# CM_MODULE.net
KiCad netlist of a schematic drawn in Altium Designer
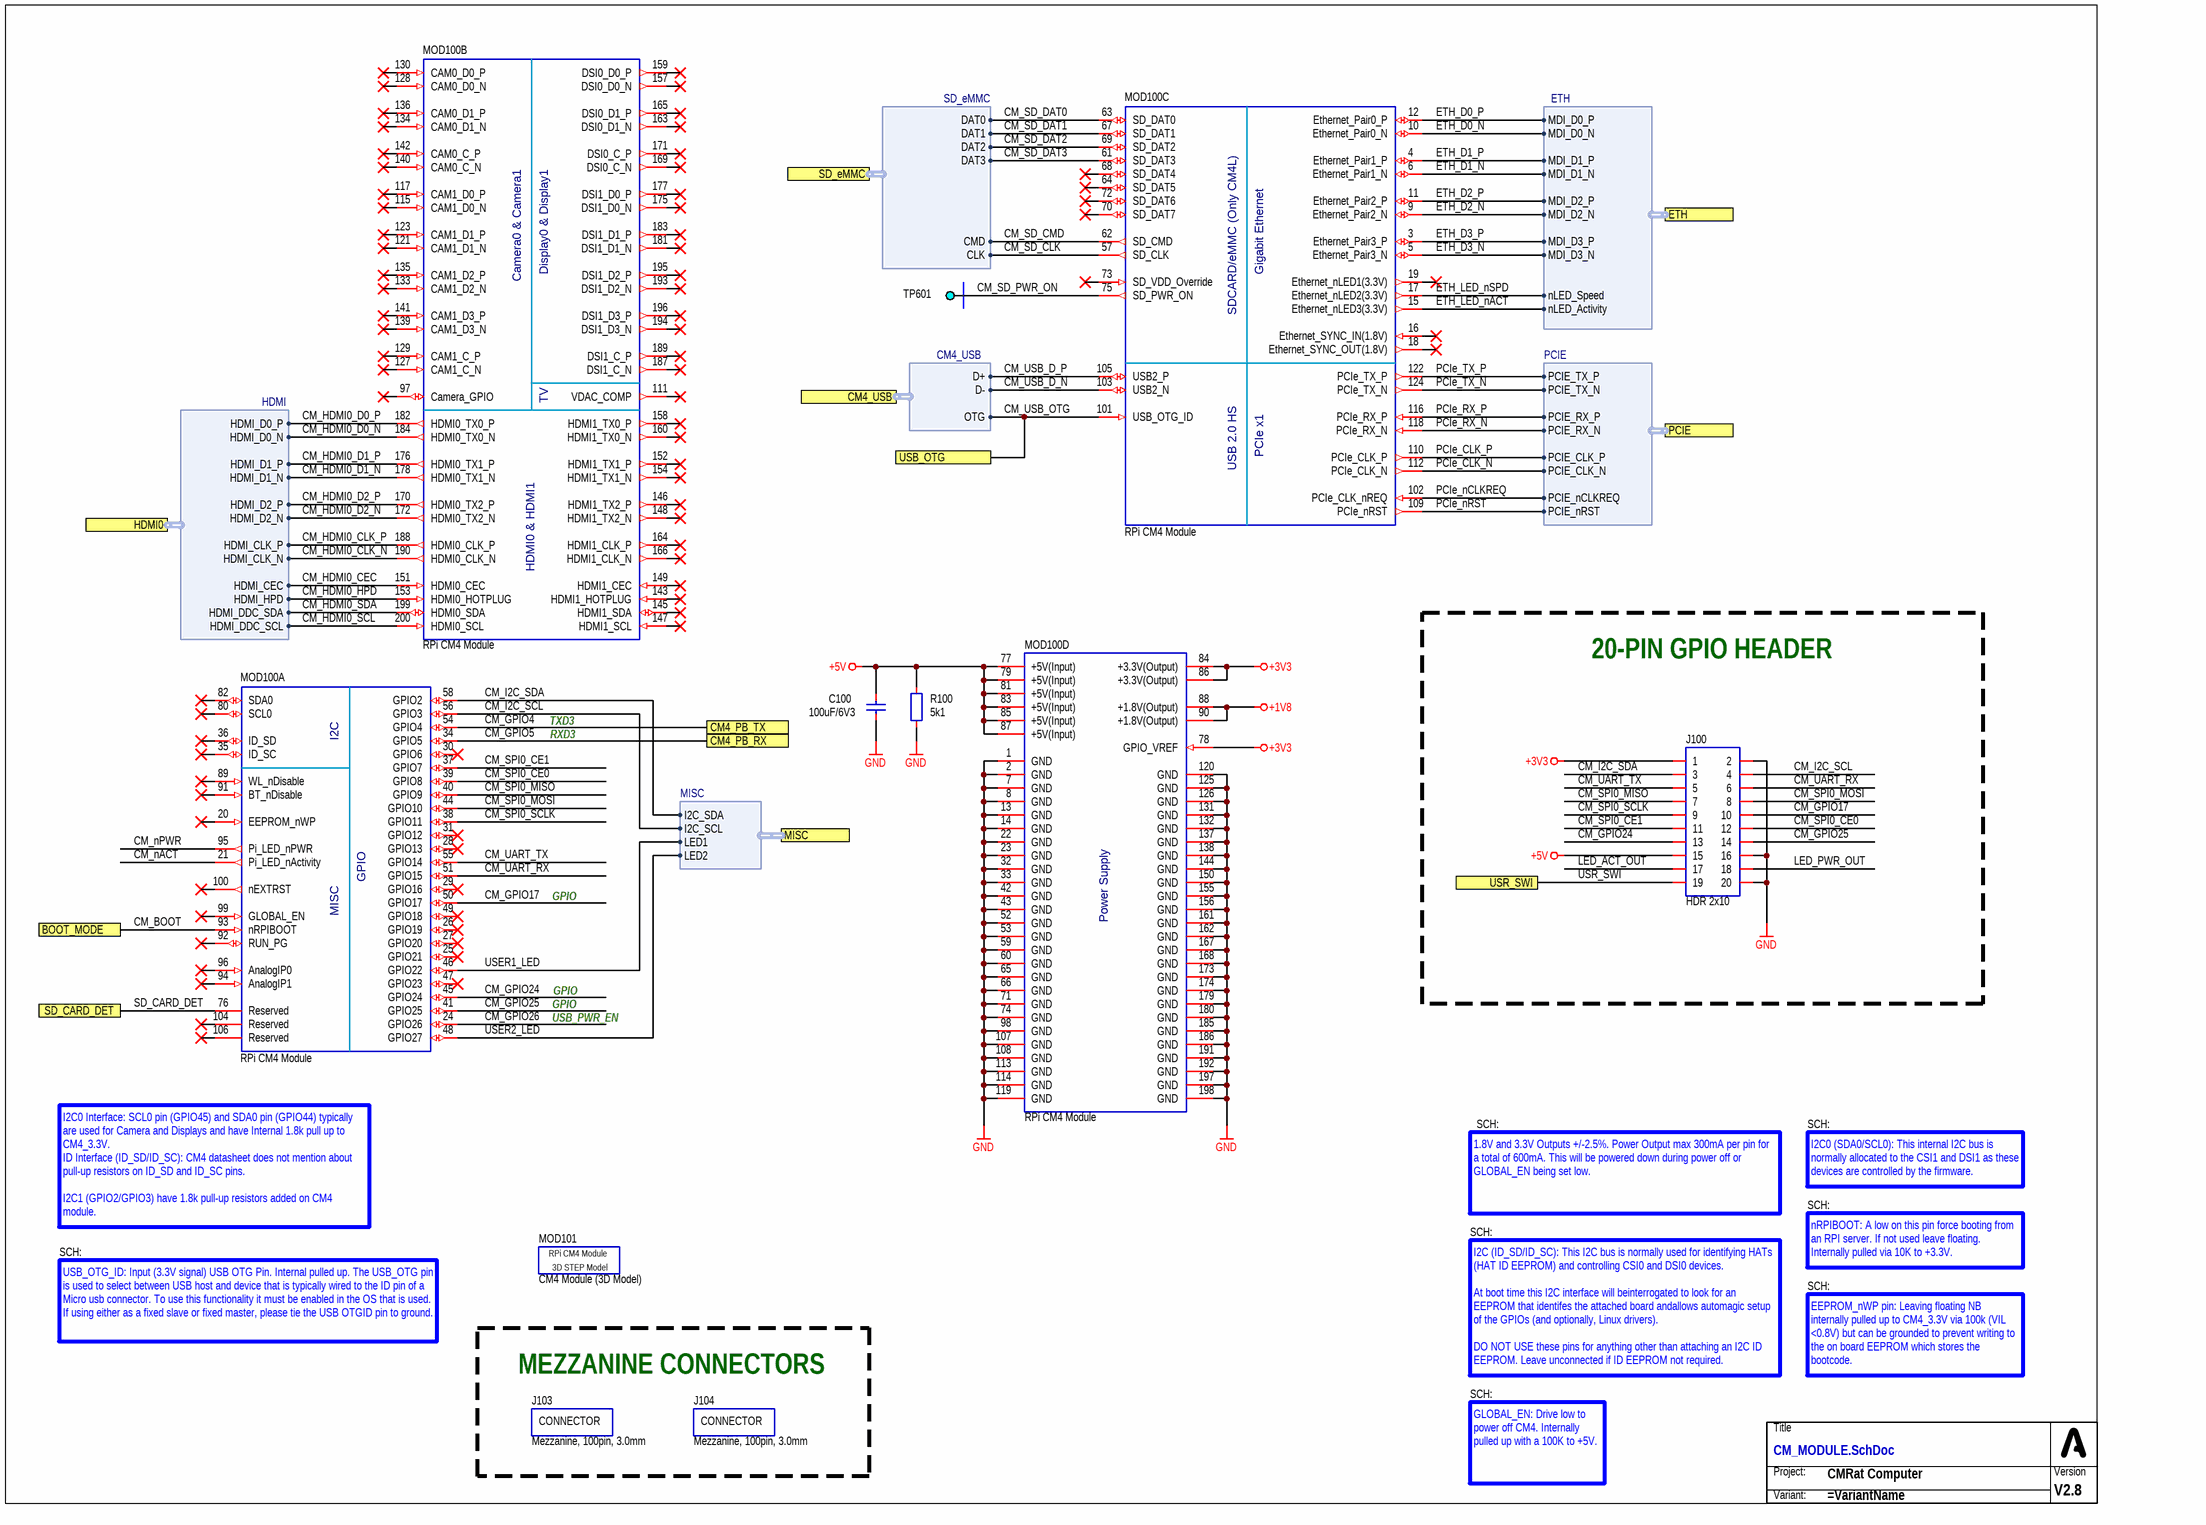
[diagram p0: CM_MODULE.SchDoc]

(export (version "E")
  (design (tool "Eeschema 10.0.6"))
  (components
    (comp (ref "C100")
      (value "100uF/6V3")
      (footprint "CAP_1206_R")
      (description "Capacitor; MLCC; 100uF 6V3")
      (fields (field (name "MANUFACTURER") "Taiyo Yuden") (field (name "MPN") "JMK316ABJ107ML-T"))
      (libsource (lib "MirFol_db_local") (part "CAP"))
    )
    (comp (ref "J100")
      (value "HDR 2x10")
      (footprint "CON_HDR_P254_2X10_STR")
      (description "CONN THT / HEADER / PITCH 2,54mm / VERTICAL / (20 PIN) 2x10")
      (fields
        (field (name "MPN") "B-2100S20P-B110")
        (field (name "MANUFACTURER") "Ckmtw(Shenzhen Cankemeng)")
      )
      (libsource (lib "MirFol_lib") (part "CON_2X10_ROW"))
    )
    (comp (ref "J103")
      (value "Mezzanine, 100pin, 3.0mm")
      (footprint "PCB_BLANK_COMP_SMD")
      (description "Connector; DF40HC(3.0)-100DS-0.4V")
      (fields (field (name "MANUFACTURER") "Hirose") (field (name "MPN") "DF40HC(3.0)-100DS-0.4V"))
      (libsource (lib "MirFol_lib") (part "BOM_CON"))
    )
    (comp (ref "J104")
      (value "Mezzanine, 100pin, 3.0mm")
      (footprint "PCB_BLANK_COMP_SMD")
      (description "Connector; DF40HC(3.0)-100DS-0.4V")
      (fields (field (name "MANUFACTURER") "Hirose") (field (name "MPN") "DF40HC(3.0)-100DS-0.4V"))
      (libsource (lib "MirFol_lib") (part "BOM_CON"))
    )
    (comp (ref "MOD100")
      (value "RPi CM4 Module")
      (footprint "MOD_RPI_CM4_SOCKET_P40_C300")
      (description "PCB Module; RPi Compute Module 4;")
      (fields (field (name "MPN") "CM4 Module") (field (name "MANUFACTURER") "Raspberry Pi Foundation"))
      (libsource (lib "MirFol_lib") (part "MOD_RPI_CM4_VAR2"))
    )
    (comp (ref "MOD101")
      (value "CM4 Module (3D Model)")
      (footprint "MOD_RPI_CM4_3D_C300_A1")
      (description "PCB Module; RPi Compute Module 4; 3D model")
      (libsource (lib "Pineberry_Lib") (part "MOD_CM4_3D_MODEL"))
    )
    (comp (ref "R100")
      (value "5k1")
      (footprint "RES_0603_R")
      (description "Resistor; Thick Film; 5k1; 1%; 100mW; 100PPM; 75V; Standard; SMD; 0603 (1608);")
      (fields (field (name "MANUFACTURER") "UNI-ROYAL(Uniroyal Elec)") (field (name "MPN") "0603WAF5101T5E"))
      (libsource (lib "MirFol_db_local") (part "RES"))
    )
    (comp (ref "TB100") (value "~") (libsource (lib "Symbols_NO_BOM") (part "SCH_TITLE_BLOCK_SIMPLE_NODATE")))
    (comp (ref "TP601")
      (value "DEBUG")
      (footprint "PCB_TP_DBG_50")
      (description "PCB Marking; Test Point (Debug);")
      (libsource (lib "MirFol_lib") (part "PCB_TP_DBG"))
    )
  )
  (nets
    (net (code "7") (name "+1V8") (class "Default")
      (node (ref "MOD100") (pin "88") (pinfunction "+1.8V(Output)_88") (pintype "power_in"))
      (node (ref "MOD100") (pin "90") (pinfunction "+1.8V(Output)_90") (pintype "power_in"))
    )
    (net (code "8") (name "+3V3") (class "Default")
      (node (ref "J100") (pin "1") (pinfunction "1_1") (pintype "passive"))
      (node (ref "MOD100") (pin "78") (pinfunction "GPIO_VREF_78") (pintype "input"))
      (node (ref "MOD100") (pin "84") (pinfunction "+3.3V(Output)_84") (pintype "power_in"))
      (node (ref "MOD100") (pin "86") (pinfunction "+3.3V(Output)_86") (pintype "power_in"))
    )
    (net (code "9") (name "+5V") (class "Default")
      (node (ref "C100") (pin "2") (pintype "passive"))
      (node (ref "J100") (pin "15") (pinfunction "15_15") (pintype "passive"))
      (node (ref "MOD100") (pin "77") (pinfunction "+5V(Input)_77") (pintype "power_in"))
      (node (ref "MOD100") (pin "79") (pinfunction "+5V(Input)_79") (pintype "power_in"))
      (node (ref "MOD100") (pin "81") (pinfunction "+5V(Input)_81") (pintype "power_in"))
      (node (ref "MOD100") (pin "83") (pinfunction "+5V(Input)_83") (pintype "power_in"))
      (node (ref "MOD100") (pin "85") (pinfunction "+5V(Input)_85") (pintype "power_in"))
      (node (ref "MOD100") (pin "87") (pinfunction "+5V(Input)_87") (pintype "power_in"))
      (node (ref "R100") (pin "1") (pinfunction "1_1") (pintype "passive"))
    )
    (net (code "10") (name "/CM_BOOT") (class "Default")
      (node (ref "MOD100") (pin "93") (pinfunction "nRPIBOOT_93") (pintype "input"))
    )
    (net (code "11") (name "/CM_GPIO4") (class "Default")
      (node (ref "MOD100") (pin "54") (pinfunction "GPIO4_54") (pintype "bidirectional"))
    )
    (net (code "12") (name "/CM_GPIO5") (class "Default")
      (node (ref "MOD100") (pin "34") (pinfunction "GPIO5_34") (pintype "bidirectional"))
    )
    (net (code "13") (name "/CM_GPIO17") (class "Default")
      (node (ref "J100") (pin "10") (pinfunction "10_10") (pintype "passive"))
      (node (ref "MOD100") (pin "50") (pinfunction "GPIO17_50") (pintype "bidirectional"))
    )
    (net (code "14") (name "/CM_GPIO24") (class "Default")
      (node (ref "J100") (pin "13") (pinfunction "13_13") (pintype "passive"))
      (node (ref "MOD100") (pin "45") (pinfunction "GPIO24_45") (pintype "bidirectional"))
    )
    (net (code "15") (name "/CM_GPIO25") (class "Default")
      (node (ref "J100") (pin "14") (pinfunction "14_14") (pintype "passive"))
      (node (ref "MOD100") (pin "41") (pinfunction "GPIO25_41") (pintype "bidirectional"))
    )
    (net (code "16") (name "/CM_GPIO26") (class "Default")
      (node (ref "MOD100") (pin "24") (pinfunction "GPIO26_24") (pintype "bidirectional"))
    )
    (net (code "17") (name "/CM_HDMI0_CEC") (class "Default")
      (node (ref "MOD100") (pin "151") (pinfunction "HDMI0_CEC_151") (pintype "input"))
    )
    (net (code "18") (name "/CM_HDMI0_CLK_N") (class "Default")
      (node (ref "MOD100") (pin "190") (pinfunction "HDMI0_CLK_N_190") (pintype "output"))
    )
    (net (code "19") (name "/CM_HDMI0_CLK_P") (class "Default")
      (node (ref "MOD100") (pin "188") (pinfunction "HDMI0_CLK_P_188") (pintype "output"))
    )
    (net (code "20") (name "/CM_HDMI0_D0_N") (class "Default")
      (node (ref "MOD100") (pin "184") (pinfunction "HDMI0_TX0_N_184") (pintype "output"))
    )
    (net (code "21") (name "/CM_HDMI0_D0_P") (class "Default")
      (node (ref "MOD100") (pin "182") (pinfunction "HDMI0_TX0_P_182") (pintype "output"))
    )
    (net (code "22") (name "/CM_HDMI0_D1_N") (class "Default")
      (node (ref "MOD100") (pin "178") (pinfunction "HDMI0_TX1_N_178") (pintype "output"))
    )
    (net (code "23") (name "/CM_HDMI0_D1_P") (class "Default")
      (node (ref "MOD100") (pin "176") (pinfunction "HDMI0_TX1_P_176") (pintype "output"))
    )
    (net (code "24") (name "/CM_HDMI0_D2_N") (class "Default")
      (node (ref "MOD100") (pin "172") (pinfunction "HDMI0_TX2_N_172") (pintype "output"))
    )
    (net (code "25") (name "/CM_HDMI0_D2_P") (class "Default")
      (node (ref "MOD100") (pin "170") (pinfunction "HDMI0_TX2_P_170") (pintype "output"))
    )
    (net (code "26") (name "/CM_HDMI0_HPD") (class "Default")
      (node (ref "MOD100") (pin "153") (pinfunction "HDMI0_HOTPLUG_153") (pintype "input"))
    )
    (net (code "27") (name "/CM_HDMI0_SCL") (class "Default")
      (node (ref "MOD100") (pin "200") (pinfunction "HDMI0_SCL_200") (pintype "input"))
    )
    (net (code "28") (name "/CM_HDMI0_SDA") (class "Default")
      (node (ref "MOD100") (pin "199") (pinfunction "HDMI0_SDA_199") (pintype "bidirectional"))
    )
    (net (code "29") (name "/CM_I2C_SCL") (class "Default")
      (node (ref "J100") (pin "4") (pinfunction "4_4") (pintype "passive"))
      (node (ref "MOD100") (pin "56") (pinfunction "GPIO3_56") (pintype "bidirectional"))
    )
    (net (code "30") (name "/CM_I2C_SDA") (class "Default")
      (node (ref "J100") (pin "3") (pinfunction "3_3") (pintype "passive"))
      (node (ref "MOD100") (pin "58") (pinfunction "GPIO2_58") (pintype "bidirectional"))
    )
    (net (code "31") (name "/CM_SD_CLK") (class "Default")
      (node (ref "MOD100") (pin "57") (pinfunction "SD_CLK_57") (pintype "output"))
    )
    (net (code "32") (name "/CM_SD_CMD") (class "Default")
      (node (ref "MOD100") (pin "62") (pinfunction "SD_CMD_62") (pintype "output"))
    )
    (net (code "33") (name "/CM_SD_DAT0") (class "Default")
      (node (ref "MOD100") (pin "63") (pinfunction "SD_DAT0_63") (pintype "bidirectional"))
    )
    (net (code "34") (name "/CM_SD_DAT1") (class "Default")
      (node (ref "MOD100") (pin "67") (pinfunction "SD_DAT1_67") (pintype "bidirectional"))
    )
    (net (code "35") (name "/CM_SD_DAT2") (class "Default")
      (node (ref "MOD100") (pin "69") (pinfunction "SD_DAT2_69") (pintype "bidirectional"))
    )
    (net (code "36") (name "/CM_SD_DAT3") (class "Default")
      (node (ref "MOD100") (pin "61") (pinfunction "SD_DAT3_61") (pintype "bidirectional"))
    )
    (net (code "37") (name "/CM_SD_PWR_ON") (class "Default")
      (node (ref "MOD100") (pin "75") (pinfunction "SD_PWR_ON_75") (pintype "output"))
      (node (ref "TP601") (pin "1") (pinfunction "1_1") (pintype "passive"))
    )
    (net (code "38") (name "/CM_SPI0_CE0") (class "Default")
      (node (ref "J100") (pin "12") (pinfunction "12_12") (pintype "passive"))
      (node (ref "MOD100") (pin "39") (pinfunction "GPIO8_39") (pintype "bidirectional"))
    )
    (net (code "39") (name "/CM_SPI0_CE1") (class "Default")
      (node (ref "J100") (pin "11") (pinfunction "11_11") (pintype "passive"))
      (node (ref "MOD100") (pin "37") (pinfunction "GPIO7_37") (pintype "bidirectional"))
    )
    (net (code "40") (name "/CM_SPI0_MISO") (class "Default")
      (node (ref "J100") (pin "7") (pinfunction "7_7") (pintype "passive"))
      (node (ref "MOD100") (pin "40") (pinfunction "GPIO9_40") (pintype "bidirectional"))
    )
    (net (code "41") (name "/CM_SPI0_MOSI") (class "Default")
      (node (ref "J100") (pin "8") (pinfunction "8_8") (pintype "passive"))
      (node (ref "MOD100") (pin "44") (pinfunction "GPIO10_44") (pintype "bidirectional"))
    )
    (net (code "42") (name "/CM_SPI0_SCLK") (class "Default")
      (node (ref "J100") (pin "9") (pinfunction "9_9") (pintype "passive"))
      (node (ref "MOD100") (pin "38") (pinfunction "GPIO11_38") (pintype "bidirectional"))
    )
    (net (code "43") (name "/CM_UART_RX") (class "Default")
      (node (ref "J100") (pin "6") (pinfunction "6_6") (pintype "passive"))
      (node (ref "MOD100") (pin "51") (pinfunction "GPIO15_51") (pintype "bidirectional"))
    )
    (net (code "44") (name "/CM_UART_TX") (class "Default")
      (node (ref "J100") (pin "5") (pinfunction "5_5") (pintype "passive"))
      (node (ref "MOD100") (pin "55") (pinfunction "GPIO14_55") (pintype "bidirectional"))
    )
    (net (code "45") (name "/CM_USB_D_N") (class "Default")
      (node (ref "MOD100") (pin "103") (pinfunction "USB2_N_103") (pintype "bidirectional"))
    )
    (net (code "46") (name "/CM_USB_D_P") (class "Default")
      (node (ref "MOD100") (pin "105") (pinfunction "USB2_P_105") (pintype "bidirectional"))
    )
    (net (code "47") (name "/CM_USB_OTG") (class "Default")
      (node (ref "MOD100") (pin "101") (pinfunction "USB_OTG_ID_101") (pintype "input"))
    )
    (net (code "48") (name "/CM_nACT") (class "Default")
      (node (ref "MOD100") (pin "21") (pinfunction "Pi_LED_nActivity_21") (pintype "output"))
    )
    (net (code "49") (name "/CM_nPWR") (class "Default")
      (node (ref "MOD100") (pin "95") (pinfunction "Pi_LED_nPWR_95") (pintype "output"))
    )
    (net (code "50") (name "/ETH_D0_N") (class "Default")
      (node (ref "MOD100") (pin "10") (pinfunction "Ethernet_Pair0_N_10") (pintype "bidirectional"))
    )
    (net (code "51") (name "/ETH_D0_P") (class "Default")
      (node (ref "MOD100") (pin "12") (pinfunction "Ethernet_Pair0_P_12") (pintype "bidirectional"))
    )
    (net (code "52") (name "/ETH_D1_N") (class "Default")
      (node (ref "MOD100") (pin "6") (pinfunction "Ethernet_Pair1_N_6") (pintype "bidirectional"))
    )
    (net (code "53") (name "/ETH_D1_P") (class "Default")
      (node (ref "MOD100") (pin "4") (pinfunction "Ethernet_Pair1_P_4") (pintype "bidirectional"))
    )
    (net (code "54") (name "/ETH_D2_N") (class "Default")
      (node (ref "MOD100") (pin "9") (pinfunction "Ethernet_Pair2_N_9") (pintype "bidirectional"))
    )
    (net (code "55") (name "/ETH_D2_P") (class "Default")
      (node (ref "MOD100") (pin "11") (pinfunction "Ethernet_Pair2_P_11") (pintype "bidirectional"))
    )
    (net (code "56") (name "/ETH_D3_N") (class "Default")
      (node (ref "MOD100") (pin "5") (pinfunction "Ethernet_Pair3_N_5") (pintype "bidirectional"))
    )
    (net (code "57") (name "/ETH_D3_P") (class "Default")
      (node (ref "MOD100") (pin "3") (pinfunction "Ethernet_Pair3_P_3") (pintype "bidirectional"))
    )
    (net (code "58") (name "/ETH_LED_nACT") (class "Default")
      (node (ref "MOD100") (pin "15") (pinfunction "Ethernet_nLED3(3.3V)_15") (pintype "output"))
    )
    (net (code "59") (name "/ETH_LED_nSPD") (class "Default")
      (node (ref "MOD100") (pin "17") (pinfunction "Ethernet_nLED2(3.3V)_17") (pintype "output"))
    )
    (net (code "60") (name "/LED_ACT_OUT") (class "Default")
      (node (ref "J100") (pin "17") (pinfunction "17_17") (pintype "passive"))
    )
    (net (code "61") (name "/LED_PWR_OUT") (class "Default")
      (node (ref "J100") (pin "18") (pinfunction "18_18") (pintype "passive"))
    )
    (net (code "62") (name "/PCIe_CLK_N") (class "Default")
      (node (ref "MOD100") (pin "112") (pinfunction "PCIe_CLK_N_112") (pintype "output"))
    )
    (net (code "63") (name "/PCIe_CLK_P") (class "Default")
      (node (ref "MOD100") (pin "110") (pinfunction "PCIe_CLK_P_110") (pintype "output"))
    )
    (net (code "64") (name "/PCIe_RX_N") (class "Default")
      (node (ref "MOD100") (pin "118") (pinfunction "PCIe_RX_N_118") (pintype "input"))
    )
    (net (code "65") (name "/PCIe_RX_P") (class "Default")
      (node (ref "MOD100") (pin "116") (pinfunction "PCIe_RX_P_116") (pintype "input"))
    )
    (net (code "66") (name "/PCIe_TX_N") (class "Default")
      (node (ref "MOD100") (pin "124") (pinfunction "PCIe_TX_N_124") (pintype "output"))
    )
    (net (code "67") (name "/PCIe_TX_P") (class "Default")
      (node (ref "MOD100") (pin "122") (pinfunction "PCIe_TX_P_122") (pintype "output"))
    )
    (net (code "68") (name "/PCIe_nCLKREQ") (class "Default")
      (node (ref "MOD100") (pin "102") (pinfunction "PCIe_CLK_nREQ_102") (pintype "input"))
    )
    (net (code "69") (name "/PCIe_nRST") (class "Default")
      (node (ref "MOD100") (pin "109") (pinfunction "PCIe_nRST_109") (pintype "output"))
    )
    (net (code "70") (name "/SD_CARD_DET") (class "Default")
      (node (ref "MOD100") (pin "76") (pinfunction "Reserved_76") (pintype "passive"))
    )
    (net (code "71") (name "/USER1_LED") (class "Default")
      (node (ref "MOD100") (pin "46") (pinfunction "GPIO22_46") (pintype "bidirectional"))
    )
    (net (code "72") (name "/USER2_LED") (class "Default")
      (node (ref "MOD100") (pin "48") (pinfunction "GPIO27_48") (pintype "bidirectional"))
    )
    (net (code "73") (name "/USR_SWI") (class "Default")
      (node (ref "J100") (pin "19") (pinfunction "19_19") (pintype "passive"))
    )
    (net (code "80") (name "GND") (class "Default")
      (node (ref "C100") (pin "1") (pintype "passive"))
      (node (ref "J100") (pin "16") (pinfunction "16_16") (pintype "passive"))
      (node (ref "J100") (pin "2") (pinfunction "2_2") (pintype "passive"))
      (node (ref "J100") (pin "20") (pinfunction "20_20") (pintype "passive"))
      (node (ref "MOD100") (pin "1") (pinfunction "GND_1") (pintype "power_in"))
      (node (ref "MOD100") (pin "107") (pinfunction "GND_107") (pintype "power_in"))
      (node (ref "MOD100") (pin "108") (pinfunction "GND_108") (pintype "power_in"))
      (node (ref "MOD100") (pin "113") (pinfunction "GND_113") (pintype "power_in"))
      (node (ref "MOD100") (pin "114") (pinfunction "GND_114") (pintype "power_in"))
      (node (ref "MOD100") (pin "119") (pinfunction "GND_119") (pintype "power_in"))
      (node (ref "MOD100") (pin "120") (pinfunction "GND_120") (pintype "power_in"))
      (node (ref "MOD100") (pin "125") (pinfunction "GND_125") (pintype "power_in"))
      (node (ref "MOD100") (pin "126") (pinfunction "GND_126") (pintype "power_in"))
      (node (ref "MOD100") (pin "13") (pinfunction "GND_13") (pintype "power_in"))
      (node (ref "MOD100") (pin "131") (pinfunction "GND_131") (pintype "power_in"))
      (node (ref "MOD100") (pin "132") (pinfunction "GND_132") (pintype "power_in"))
      (node (ref "MOD100") (pin "137") (pinfunction "GND_137") (pintype "power_in"))
      (node (ref "MOD100") (pin "138") (pinfunction "GND_138") (pintype "power_in"))
      (node (ref "MOD100") (pin "14") (pinfunction "GND_14") (pintype "power_in"))
      (node (ref "MOD100") (pin "144") (pinfunction "GND_144") (pintype "power_in"))
      (node (ref "MOD100") (pin "150") (pinfunction "GND_150") (pintype "power_in"))
      (node (ref "MOD100") (pin "155") (pinfunction "GND_155") (pintype "power_in"))
      (node (ref "MOD100") (pin "156") (pinfunction "GND_156") (pintype "power_in"))
      (node (ref "MOD100") (pin "161") (pinfunction "GND_161") (pintype "power_in"))
      (node (ref "MOD100") (pin "162") (pinfunction "GND_162") (pintype "power_in"))
      (node (ref "MOD100") (pin "167") (pinfunction "GND_167") (pintype "power_in"))
      (node (ref "MOD100") (pin "168") (pinfunction "GND_168") (pintype "power_in"))
      (node (ref "MOD100") (pin "173") (pinfunction "GND_173") (pintype "power_in"))
      (node (ref "MOD100") (pin "174") (pinfunction "GND_174") (pintype "power_in"))
      (node (ref "MOD100") (pin "179") (pinfunction "GND_179") (pintype "power_in"))
      (node (ref "MOD100") (pin "180") (pinfunction "GND_180") (pintype "power_in"))
      (node (ref "MOD100") (pin "185") (pinfunction "GND_185") (pintype "power_in"))
      (node (ref "MOD100") (pin "186") (pinfunction "GND_186") (pintype "power_in"))
      (node (ref "MOD100") (pin "191") (pinfunction "GND_191") (pintype "power_in"))
      (node (ref "MOD100") (pin "192") (pinfunction "GND_192") (pintype "power_in"))
      (node (ref "MOD100") (pin "197") (pinfunction "GND_197") (pintype "power_in"))
      (node (ref "MOD100") (pin "198") (pinfunction "GND_198") (pintype "power_in"))
      (node (ref "MOD100") (pin "2") (pinfunction "GND_2") (pintype "power_in"))
      (node (ref "MOD100") (pin "22") (pinfunction "GND_22") (pintype "power_in"))
      (node (ref "MOD100") (pin "23") (pinfunction "GND_23") (pintype "power_in"))
      (node (ref "MOD100") (pin "32") (pinfunction "GND_32") (pintype "power_in"))
      (node (ref "MOD100") (pin "33") (pinfunction "GND_33") (pintype "power_in"))
      (node (ref "MOD100") (pin "42") (pinfunction "GND_42") (pintype "power_in"))
      (node (ref "MOD100") (pin "43") (pinfunction "GND_43") (pintype "power_in"))
      (node (ref "MOD100") (pin "52") (pinfunction "GND_52") (pintype "power_in"))
      (node (ref "MOD100") (pin "53") (pinfunction "GND_53") (pintype "power_in"))
      (node (ref "MOD100") (pin "59") (pinfunction "GND_59") (pintype "power_in"))
      (node (ref "MOD100") (pin "60") (pinfunction "GND_60") (pintype "power_in"))
      (node (ref "MOD100") (pin "65") (pinfunction "GND_65") (pintype "power_in"))
      (node (ref "MOD100") (pin "66") (pinfunction "GND_66") (pintype "power_in"))
      (node (ref "MOD100") (pin "7") (pinfunction "GND_7") (pintype "power_in"))
      (node (ref "MOD100") (pin "71") (pinfunction "GND_71") (pintype "power_in"))
      (node (ref "MOD100") (pin "74") (pinfunction "GND_74") (pintype "power_in"))
      (node (ref "MOD100") (pin "8") (pinfunction "GND_8") (pintype "power_in"))
      (node (ref "MOD100") (pin "98") (pinfunction "GND_98") (pintype "power_in"))
      (node (ref "R100") (pin "2") (pinfunction "2_2") (pintype "passive"))
    )
    (net (code "81") (name "unconnected-(MOD100A-AnalogIP0-Pad96)") (class "Default")
      (node (ref "MOD100") (pin "96") (pinfunction "AnalogIP0_96") (pintype "input+no_connect"))
    )
    (net (code "82") (name "unconnected-(MOD100A-AnalogIP1-Pad94)") (class "Default")
      (node (ref "MOD100") (pin "94") (pinfunction "AnalogIP1_94") (pintype "input+no_connect"))
    )
    (net (code "83") (name "unconnected-(MOD100A-BT_nDisable-Pad91)") (class "Default")
      (node (ref "MOD100") (pin "91") (pinfunction "BT_nDisable_91") (pintype "input+no_connect"))
    )
    (net (code "84") (name "unconnected-(MOD100A-EEPROM_nWP-Pad20)") (class "Default")
      (node (ref "MOD100") (pin "20") (pinfunction "EEPROM_nWP_20") (pintype "input+no_connect"))
    )
    (net (code "85") (name "unconnected-(MOD100A-GLOBAL_EN-Pad99)") (class "Default")
      (node (ref "MOD100") (pin "99") (pinfunction "GLOBAL_EN_99") (pintype "input+no_connect"))
    )
    (net (code "86") (name "unconnected-(MOD100A-GPIO6-Pad30)") (class "Default")
      (node (ref "MOD100") (pin "30") (pinfunction "GPIO6_30") (pintype "bidirectional+no_connect"))
    )
    (net (code "87") (name "unconnected-(MOD100A-GPIO12-Pad31)") (class "Default")
      (node (ref "MOD100") (pin "31") (pinfunction "GPIO12_31") (pintype "bidirectional+no_connect"))
    )
    (net (code "88") (name "unconnected-(MOD100A-GPIO13-Pad28)") (class "Default")
      (node (ref "MOD100") (pin "28") (pinfunction "GPIO13_28") (pintype "bidirectional+no_connect"))
    )
    (net (code "89") (name "unconnected-(MOD100A-GPIO16-Pad29)") (class "Default")
      (node (ref "MOD100") (pin "29") (pinfunction "GPIO16_29") (pintype "bidirectional+no_connect"))
    )
    (net (code "90") (name "unconnected-(MOD100A-GPIO18-Pad49)") (class "Default")
      (node (ref "MOD100") (pin "49") (pinfunction "GPIO18_49") (pintype "bidirectional+no_connect"))
    )
    (net (code "91") (name "unconnected-(MOD100A-GPIO19-Pad26)") (class "Default")
      (node (ref "MOD100") (pin "26") (pinfunction "GPIO19_26") (pintype "bidirectional+no_connect"))
    )
    (net (code "92") (name "unconnected-(MOD100A-GPIO20-Pad27)") (class "Default")
      (node (ref "MOD100") (pin "27") (pinfunction "GPIO20_27") (pintype "bidirectional+no_connect"))
    )
    (net (code "93") (name "unconnected-(MOD100A-GPIO21-Pad25)") (class "Default")
      (node (ref "MOD100") (pin "25") (pinfunction "GPIO21_25") (pintype "bidirectional+no_connect"))
    )
    (net (code "94") (name "unconnected-(MOD100A-GPIO23-Pad47)") (class "Default")
      (node (ref "MOD100") (pin "47") (pinfunction "GPIO23_47") (pintype "bidirectional+no_connect"))
    )
    (net (code "95") (name "unconnected-(MOD100A-ID_SC-Pad35)") (class "Default")
      (node (ref "MOD100") (pin "35") (pinfunction "ID_SC_35") (pintype "bidirectional+no_connect"))
    )
    (net (code "96") (name "unconnected-(MOD100A-ID_SD-Pad36)") (class "Default")
      (node (ref "MOD100") (pin "36") (pinfunction "ID_SD_36") (pintype "bidirectional+no_connect"))
    )
    (net (code "97") (name "unconnected-(MOD100A-RUN_PG-Pad92)") (class "Default")
      (node (ref "MOD100") (pin "92") (pinfunction "RUN_PG_92") (pintype "bidirectional+no_connect"))
    )
    (net (code "98") (name "unconnected-(MOD100A-Reserved-Pad104)") (class "Default")
      (node (ref "MOD100") (pin "104") (pinfunction "Reserved_104") (pintype "passive+no_connect"))
    )
    (net (code "99") (name "unconnected-(MOD100A-Reserved-Pad106)") (class "Default")
      (node (ref "MOD100") (pin "106") (pinfunction "Reserved_106") (pintype "passive+no_connect"))
    )
    (net (code "100") (name "unconnected-(MOD100A-SCL0-Pad80)") (class "Default")
      (node (ref "MOD100") (pin "80") (pinfunction "SCL0_80") (pintype "bidirectional+no_connect"))
    )
    (net (code "101") (name "unconnected-(MOD100A-SDA0-Pad82)") (class "Default")
      (node (ref "MOD100") (pin "82") (pinfunction "SDA0_82") (pintype "bidirectional+no_connect"))
    )
    (net (code "102") (name "unconnected-(MOD100A-WL_nDisable-Pad89)") (class "Default")
      (node (ref "MOD100") (pin "89") (pinfunction "WL_nDisable_89") (pintype "input+no_connect"))
    )
    (net (code "103") (name "unconnected-(MOD100A-nEXTRST-Pad100)") (class "Default")
      (node (ref "MOD100") (pin "100") (pinfunction "nEXTRST_100") (pintype "output+no_connect"))
    )
    (net (code "104") (name "unconnected-(MOD100B-CAM0_C_N-Pad140)") (class "Default")
      (node (ref "MOD100") (pin "140") (pinfunction "CAM0_C_N_140") (pintype "input+no_connect"))
    )
    (net (code "105") (name "unconnected-(MOD100B-CAM0_C_P-Pad142)") (class "Default")
      (node (ref "MOD100") (pin "142") (pinfunction "CAM0_C_P_142") (pintype "input+no_connect"))
    )
    (net (code "106") (name "unconnected-(MOD100B-CAM0_D0_N-Pad128)") (class "Default")
      (node (ref "MOD100") (pin "128") (pinfunction "CAM0_D0_N_128") (pintype "input+no_connect"))
    )
    (net (code "107") (name "unconnected-(MOD100B-CAM0_D0_P-Pad130)") (class "Default")
      (node (ref "MOD100") (pin "130") (pinfunction "CAM0_D0_P_130") (pintype "input+no_connect"))
    )
    (net (code "108") (name "unconnected-(MOD100B-CAM0_D1_N-Pad134)") (class "Default")
      (node (ref "MOD100") (pin "134") (pinfunction "CAM0_D1_N_134") (pintype "input+no_connect"))
    )
    (net (code "109") (name "unconnected-(MOD100B-CAM0_D1_P-Pad136)") (class "Default")
      (node (ref "MOD100") (pin "136") (pinfunction "CAM0_D1_P_136") (pintype "input+no_connect"))
    )
    (net (code "110") (name "unconnected-(MOD100B-CAM1_C_N-Pad127)") (class "Default")
      (node (ref "MOD100") (pin "127") (pinfunction "CAM1_C_N_127") (pintype "input+no_connect"))
    )
    (net (code "111") (name "unconnected-(MOD100B-CAM1_C_P-Pad129)") (class "Default")
      (node (ref "MOD100") (pin "129") (pinfunction "CAM1_C_P_129") (pintype "input+no_connect"))
    )
    (net (code "112") (name "unconnected-(MOD100B-CAM1_D0_N-Pad115)") (class "Default")
      (node (ref "MOD100") (pin "115") (pinfunction "CAM1_D0_N_115") (pintype "input+no_connect"))
    )
    (net (code "113") (name "unconnected-(MOD100B-CAM1_D0_P-Pad117)") (class "Default")
      (node (ref "MOD100") (pin "117") (pinfunction "CAM1_D0_P_117") (pintype "input+no_connect"))
    )
    (net (code "114") (name "unconnected-(MOD100B-CAM1_D1_N-Pad121)") (class "Default")
      (node (ref "MOD100") (pin "121") (pinfunction "CAM1_D1_N_121") (pintype "input+no_connect"))
    )
    (net (code "115") (name "unconnected-(MOD100B-CAM1_D1_P-Pad123)") (class "Default")
      (node (ref "MOD100") (pin "123") (pinfunction "CAM1_D1_P_123") (pintype "input+no_connect"))
    )
    (net (code "116") (name "unconnected-(MOD100B-CAM1_D2_N-Pad133)") (class "Default")
      (node (ref "MOD100") (pin "133") (pinfunction "CAM1_D2_N_133") (pintype "input+no_connect"))
    )
    (net (code "117") (name "unconnected-(MOD100B-CAM1_D2_P-Pad135)") (class "Default")
      (node (ref "MOD100") (pin "135") (pinfunction "CAM1_D2_P_135") (pintype "input+no_connect"))
    )
    (net (code "118") (name "unconnected-(MOD100B-CAM1_D3_N-Pad139)") (class "Default")
      (node (ref "MOD100") (pin "139") (pinfunction "CAM1_D3_N_139") (pintype "input+no_connect"))
    )
    (net (code "119") (name "unconnected-(MOD100B-CAM1_D3_P-Pad141)") (class "Default")
      (node (ref "MOD100") (pin "141") (pinfunction "CAM1_D3_P_141") (pintype "input+no_connect"))
    )
    (net (code "120") (name "unconnected-(MOD100B-Camera_GPIO-Pad97)") (class "Default")
      (node (ref "MOD100") (pin "97") (pinfunction "Camera_GPIO_97") (pintype "bidirectional+no_connect"))
    )
    (net (code "121") (name "unconnected-(MOD100B-DSI0_C_N-Pad169)") (class "Default")
      (node (ref "MOD100") (pin "169") (pinfunction "DSI0_C_N_169") (pintype "output+no_connect"))
    )
    (net (code "122") (name "unconnected-(MOD100B-DSI0_C_P-Pad171)") (class "Default")
      (node (ref "MOD100") (pin "171") (pinfunction "DSI0_C_P_171") (pintype "output+no_connect"))
    )
    (net (code "123") (name "unconnected-(MOD100B-DSI0_D0_N-Pad157)") (class "Default")
      (node (ref "MOD100") (pin "157") (pinfunction "DSI0_D0_N_157") (pintype "output+no_connect"))
    )
    (net (code "124") (name "unconnected-(MOD100B-DSI0_D0_P-Pad159)") (class "Default")
      (node (ref "MOD100") (pin "159") (pinfunction "DSI0_D0_P_159") (pintype "output+no_connect"))
    )
    (net (code "125") (name "unconnected-(MOD100B-DSI0_D1_N-Pad163)") (class "Default")
      (node (ref "MOD100") (pin "163") (pinfunction "DSI0_D1_N_163") (pintype "output+no_connect"))
    )
    (net (code "126") (name "unconnected-(MOD100B-DSI0_D1_P-Pad165)") (class "Default")
      (node (ref "MOD100") (pin "165") (pinfunction "DSI0_D1_P_165") (pintype "output+no_connect"))
    )
    (net (code "127") (name "unconnected-(MOD100B-DSI1_C_N-Pad187)") (class "Default")
      (node (ref "MOD100") (pin "187") (pinfunction "DSI1_C_N_187") (pintype "output+no_connect"))
    )
    (net (code "128") (name "unconnected-(MOD100B-DSI1_C_P-Pad189)") (class "Default")
      (node (ref "MOD100") (pin "189") (pinfunction "DSI1_C_P_189") (pintype "output+no_connect"))
    )
    (net (code "129") (name "unconnected-(MOD100B-DSI1_D0_N-Pad175)") (class "Default")
      (node (ref "MOD100") (pin "175") (pinfunction "DSI1_D0_N_175") (pintype "output+no_connect"))
    )
    (net (code "130") (name "unconnected-(MOD100B-DSI1_D0_P-Pad177)") (class "Default")
      (node (ref "MOD100") (pin "177") (pinfunction "DSI1_D0_P_177") (pintype "output+no_connect"))
    )
    (net (code "131") (name "unconnected-(MOD100B-DSI1_D1_N-Pad181)") (class "Default")
      (node (ref "MOD100") (pin "181") (pinfunction "DSI1_D1_N_181") (pintype "output+no_connect"))
    )
    (net (code "132") (name "unconnected-(MOD100B-DSI1_D1_P-Pad183)") (class "Default")
      (node (ref "MOD100") (pin "183") (pinfunction "DSI1_D1_P_183") (pintype "output+no_connect"))
    )
    (net (code "133") (name "unconnected-(MOD100B-DSI1_D2_N-Pad193)") (class "Default")
      (node (ref "MOD100") (pin "193") (pinfunction "DSI1_D2_N_193") (pintype "output+no_connect"))
    )
    (net (code "134") (name "unconnected-(MOD100B-DSI1_D2_P-Pad195)") (class "Default")
      (node (ref "MOD100") (pin "195") (pinfunction "DSI1_D2_P_195") (pintype "output+no_connect"))
    )
    (net (code "135") (name "unconnected-(MOD100B-DSI1_D3_N-Pad194)") (class "Default")
      (node (ref "MOD100") (pin "194") (pinfunction "DSI1_D3_N_194") (pintype "output+no_connect"))
    )
    (net (code "136") (name "unconnected-(MOD100B-DSI1_D3_P-Pad196)") (class "Default")
      (node (ref "MOD100") (pin "196") (pinfunction "DSI1_D3_P_196") (pintype "output+no_connect"))
    )
    (net (code "137") (name "unconnected-(MOD100B-HDMI1_CEC-Pad149)") (class "Default")
      (node (ref "MOD100") (pin "149") (pinfunction "HDMI1_CEC_149") (pintype "input+no_connect"))
    )
    (net (code "138") (name "unconnected-(MOD100B-HDMI1_CLK_N-Pad166)") (class "Default")
      (node (ref "MOD100") (pin "166") (pinfunction "HDMI1_CLK_N_166") (pintype "output+no_connect"))
    )
    (net (code "139") (name "unconnected-(MOD100B-HDMI1_CLK_P-Pad164)") (class "Default")
      (node (ref "MOD100") (pin "164") (pinfunction "HDMI1_CLK_P_164") (pintype "output+no_connect"))
    )
    (net (code "140") (name "unconnected-(MOD100B-HDMI1_HOTPLUG-Pad143)") (class "Default")
      (node (ref "MOD100") (pin "143") (pinfunction "HDMI1_HOTPLUG_143") (pintype "input+no_connect"))
    )
    (net (code "141") (name "unconnected-(MOD100B-HDMI1_SCL-Pad147)") (class "Default")
      (node (ref "MOD100") (pin "147") (pinfunction "HDMI1_SCL_147") (pintype "input+no_connect"))
    )
    (net (code "142") (name "unconnected-(MOD100B-HDMI1_SDA-Pad145)") (class "Default")
      (node (ref "MOD100") (pin "145") (pinfunction "HDMI1_SDA_145") (pintype "bidirectional+no_connect"))
    )
    (net (code "143") (name "unconnected-(MOD100B-HDMI1_TX0_N-Pad160)") (class "Default")
      (node (ref "MOD100") (pin "160") (pinfunction "HDMI1_TX0_N_160") (pintype "output+no_connect"))
    )
    (net (code "144") (name "unconnected-(MOD100B-HDMI1_TX0_P-Pad158)") (class "Default")
      (node (ref "MOD100") (pin "158") (pinfunction "HDMI1_TX0_P_158") (pintype "output+no_connect"))
    )
    (net (code "145") (name "unconnected-(MOD100B-HDMI1_TX1_N-Pad154)") (class "Default")
      (node (ref "MOD100") (pin "154") (pinfunction "HDMI1_TX1_N_154") (pintype "output+no_connect"))
    )
    (net (code "146") (name "unconnected-(MOD100B-HDMI1_TX1_P-Pad152)") (class "Default")
      (node (ref "MOD100") (pin "152") (pinfunction "HDMI1_TX1_P_152") (pintype "output+no_connect"))
    )
    (net (code "147") (name "unconnected-(MOD100B-HDMI1_TX2_N-Pad148)") (class "Default")
      (node (ref "MOD100") (pin "148") (pinfunction "HDMI1_TX2_N_148") (pintype "output+no_connect"))
    )
    (net (code "148") (name "unconnected-(MOD100B-HDMI1_TX2_P-Pad146)") (class "Default")
      (node (ref "MOD100") (pin "146") (pinfunction "HDMI1_TX2_P_146") (pintype "output+no_connect"))
    )
    (net (code "149") (name "unconnected-(MOD100B-VDAC_COMP-Pad111)") (class "Default")
      (node (ref "MOD100") (pin "111") (pinfunction "VDAC_COMP_111") (pintype "output+no_connect"))
    )
    (net (code "150") (name "unconnected-(MOD100C-Ethernet_SYNC_IN(1.8V)-Pad16)") (class "Default")
      (node (ref "MOD100") (pin "16") (pinfunction "Ethernet_SYNC_IN(1.8V)_16") (pintype "input+no_connect"))
    )
    (net (code "151") (name "unconnected-(MOD100C-Ethernet_SYNC_OUT(1.8V)-Pad18)") (class "Default")
      (node (ref "MOD100") (pin "18") (pinfunction "Ethernet_SYNC_OUT(1.8V)_18") (pintype "output+no_connect"))
    )
    (net (code "152") (name "unconnected-(MOD100C-Ethernet_nLED1(3.3V)-Pad19)") (class "Default")
      (node (ref "MOD100") (pin "19") (pinfunction "Ethernet_nLED1(3.3V)_19") (pintype "output+no_connect"))
    )
    (net (code "153") (name "unconnected-(MOD100C-SD_DAT4-Pad68)") (class "Default")
      (node (ref "MOD100") (pin "68") (pinfunction "SD_DAT4_68") (pintype "bidirectional+no_connect"))
    )
    (net (code "154") (name "unconnected-(MOD100C-SD_DAT5-Pad64)") (class "Default")
      (node (ref "MOD100") (pin "64") (pinfunction "SD_DAT5_64") (pintype "bidirectional+no_connect"))
    )
    (net (code "155") (name "unconnected-(MOD100C-SD_DAT6-Pad72)") (class "Default")
      (node (ref "MOD100") (pin "72") (pinfunction "SD_DAT6_72") (pintype "bidirectional+no_connect"))
    )
    (net (code "156") (name "unconnected-(MOD100C-SD_DAT7-Pad70)") (class "Default")
      (node (ref "MOD100") (pin "70") (pinfunction "SD_DAT7_70") (pintype "bidirectional+no_connect"))
    )
    (net (code "157") (name "unconnected-(MOD100C-SD_VDD_Override-Pad73)") (class "Default")
      (node (ref "MOD100") (pin "73") (pinfunction "SD_VDD_Override_73") (pintype "input+no_connect"))
    )
  )
)
